# Trainiii_aux.net
KiCad netlist of a schematic drawn in EAGLE
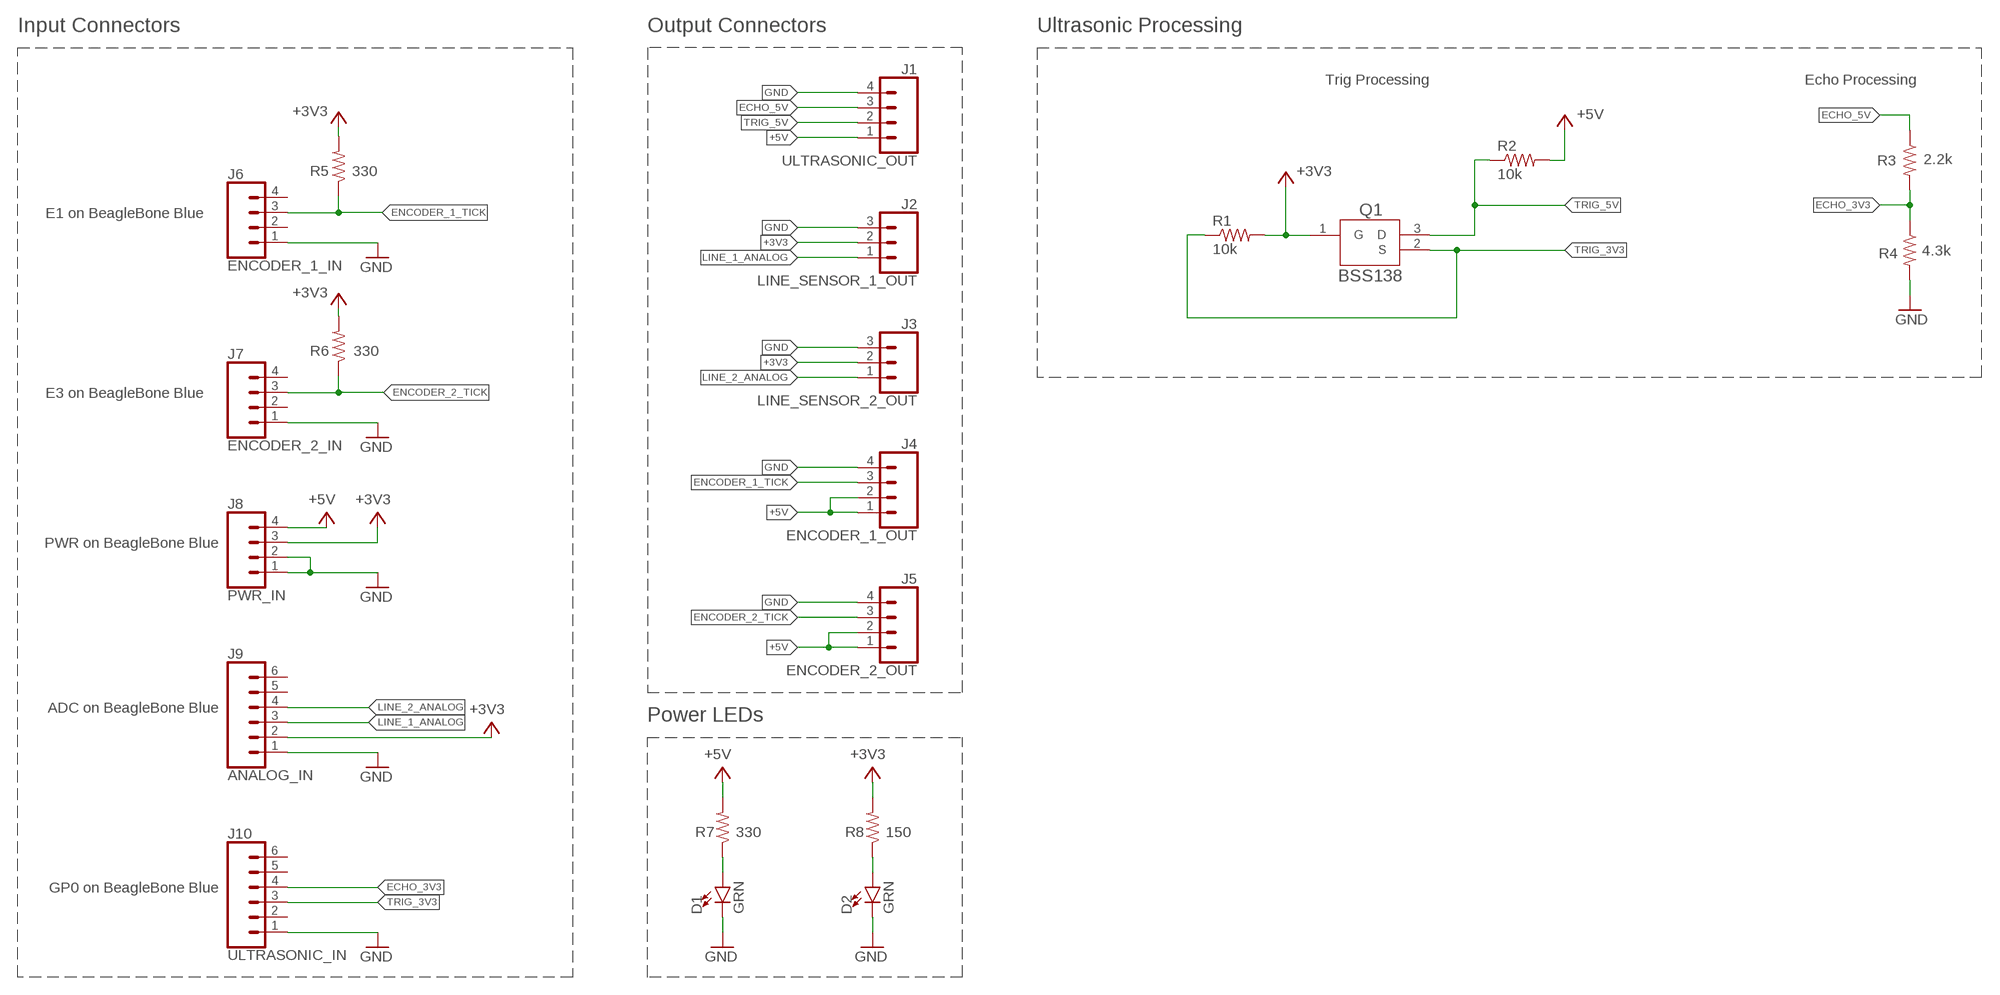
[diagram p0: schematic, sheet 1]

(export (version "E")
  (design (tool "Eeschema 10.0.6"))
  (components
    (comp (ref "D1")
      (value "GRN")
      (footprint "eagle-import:LED-0603")
      (libsource (lib "eagle-import") (part "LED0603"))
    )
    (comp (ref "D2")
      (value "GRN")
      (footprint "eagle-import:LED-0603")
      (libsource (lib "eagle-import") (part "LED0603"))
    )
    (comp (ref "J1")
      (value "ULTRASONIC_OUT")
      (footprint "eagle-import:1X04")
      (libsource (lib "eagle-import") (part "CONN_04"))
    )
    (comp (ref "J2")
      (value "LINE_SENSOR_1_OUT")
      (footprint "eagle-import:1X03")
      (libsource (lib "eagle-import") (part "CONN_03"))
    )
    (comp (ref "J3")
      (value "LINE_SENSOR_2_OUT")
      (footprint "eagle-import:1X03")
      (libsource (lib "eagle-import") (part "CONN_03"))
    )
    (comp (ref "J4")
      (value "ENCODER_1_OUT")
      (footprint "eagle-import:1X04")
      (libsource (lib "eagle-import") (part "CONN_04"))
    )
    (comp (ref "J5")
      (value "ENCODER_2_OUT")
      (footprint "eagle-import:1X04")
      (libsource (lib "eagle-import") (part "CONN_04"))
    )
    (comp (ref "J6")
      (value "ENCODER_1_IN")
      (footprint "eagle-import:1X04")
      (libsource (lib "eagle-import") (part "CONN_04"))
    )
    (comp (ref "J7")
      (value "ENCODER_2_IN")
      (footprint "eagle-import:1X04")
      (libsource (lib "eagle-import") (part "CONN_04"))
    )
    (comp (ref "J8")
      (value "PWR_IN")
      (footprint "eagle-import:1X04")
      (libsource (lib "eagle-import") (part "CONN_04"))
    )
    (comp (ref "J9")
      (value "ANALOG_IN")
      (footprint "eagle-import:1X06")
      (libsource (lib "eagle-import") (part "CONN_06SILK_FEMALE_PTH"))
    )
    (comp (ref "J10")
      (value "ULTRASONIC_IN")
      (footprint "eagle-import:1X06")
      (libsource (lib "eagle-import") (part "CONN_06SILK_FEMALE_PTH"))
    )
    (comp (ref "Q1")
      (value "BSS138")
      (footprint "eagle-import:SOT-23-3L")
      (libsource (lib "eagle-import") (part "BSS138"))
    )
    (comp (ref "R1")
      (value "10k")
      (footprint "eagle-import:R0603")
      (libsource (lib "eagle-import") (part "R-US_R0603"))
    )
    (comp (ref "R2")
      (value "10k")
      (footprint "eagle-import:R0603")
      (libsource (lib "eagle-import") (part "R-US_R0603"))
    )
    (comp (ref "R3")
      (value "2.2k")
      (footprint "eagle-import:R0603")
      (libsource (lib "eagle-import") (part "R-US_R0603"))
    )
    (comp (ref "R4")
      (value "4.3k")
      (footprint "eagle-import:R0603")
      (libsource (lib "eagle-import") (part "R-US_R0603"))
    )
    (comp (ref "R5")
      (value "330")
      (footprint "eagle-import:R0603")
      (libsource (lib "eagle-import") (part "R-US_R0603"))
    )
    (comp (ref "R6")
      (value "330")
      (footprint "eagle-import:R0603")
      (libsource (lib "eagle-import") (part "R-US_R0603"))
    )
    (comp (ref "R7")
      (value "330")
      (footprint "eagle-import:R0603")
      (libsource (lib "eagle-import") (part "R-US_R0603"))
    )
    (comp (ref "R8")
      (value "150")
      (footprint "eagle-import:R0603")
      (libsource (lib "eagle-import") (part "R-US_R0603"))
    )
  )
  (nets
    (net (code "1") (name "+3V3") (class "Default")
      (node (ref "J2") (pin "2") (pinfunction "2_2") (pintype "passive"))
      (node (ref "J3") (pin "2") (pinfunction "2_2") (pintype "passive"))
      (node (ref "J8") (pin "3") (pinfunction "3_3") (pintype "passive"))
      (node (ref "J9") (pin "2") (pinfunction "2_2") (pintype "passive"))
      (node (ref "Q1") (pin "1") (pinfunction "G_1") (pintype "power_in"))
      (node (ref "R1") (pin "2") (pinfunction "2_2") (pintype "passive"))
      (node (ref "R5") (pin "2") (pinfunction "2_2") (pintype "passive"))
      (node (ref "R6") (pin "2") (pinfunction "2_2") (pintype "passive"))
      (node (ref "R8") (pin "2") (pinfunction "2_2") (pintype "passive"))
    )
    (net (code "2") (name "+5V") (class "Default")
      (node (ref "J1") (pin "1") (pinfunction "1_1") (pintype "passive"))
      (node (ref "J4") (pin "1") (pinfunction "1_1") (pintype "passive"))
      (node (ref "J4") (pin "2") (pinfunction "2_2") (pintype "passive"))
      (node (ref "J5") (pin "1") (pinfunction "1_1") (pintype "passive"))
      (node (ref "J5") (pin "2") (pinfunction "2_2") (pintype "passive"))
      (node (ref "J8") (pin "4") (pinfunction "4_4") (pintype "passive"))
      (node (ref "R2") (pin "2") (pinfunction "2_2") (pintype "passive"))
      (node (ref "R7") (pin "2") (pinfunction "2_2") (pintype "passive"))
    )
    (net (code "3") (name "ECHO_3V3") (class "Default")
      (node (ref "J10") (pin "4") (pinfunction "4_4") (pintype "passive"))
      (node (ref "R3") (pin "2") (pinfunction "2_2") (pintype "passive"))
      (node (ref "R4") (pin "1") (pinfunction "1_1") (pintype "passive"))
    )
    (net (code "4") (name "ECHO_5V") (class "Default")
      (node (ref "J1") (pin "3") (pinfunction "3_3") (pintype "passive"))
      (node (ref "R3") (pin "1") (pinfunction "1_1") (pintype "passive"))
    )
    (net (code "5") (name "ENCODER_1_TICK") (class "Default")
      (node (ref "J4") (pin "3") (pinfunction "3_3") (pintype "passive"))
      (node (ref "J6") (pin "3") (pinfunction "3_3") (pintype "passive"))
      (node (ref "R5") (pin "1") (pinfunction "1_1") (pintype "passive"))
    )
    (net (code "6") (name "ENCODER_2_TICK") (class "Default")
      (node (ref "J5") (pin "3") (pinfunction "3_3") (pintype "passive"))
      (node (ref "J7") (pin "3") (pinfunction "3_3") (pintype "passive"))
      (node (ref "R6") (pin "1") (pinfunction "1_1") (pintype "passive"))
    )
    (net (code "7") (name "GND") (class "Default")
      (node (ref "D1") (pin "C") (pinfunction "C_C") (pintype "passive"))
      (node (ref "D2") (pin "C") (pinfunction "C_C") (pintype "passive"))
      (node (ref "J1") (pin "4") (pinfunction "4_4") (pintype "passive"))
      (node (ref "J10") (pin "1") (pinfunction "1_1") (pintype "passive"))
      (node (ref "J2") (pin "3") (pinfunction "3_3") (pintype "passive"))
      (node (ref "J3") (pin "3") (pinfunction "3_3") (pintype "passive"))
      (node (ref "J4") (pin "4") (pinfunction "4_4") (pintype "passive"))
      (node (ref "J5") (pin "4") (pinfunction "4_4") (pintype "passive"))
      (node (ref "J6") (pin "1") (pinfunction "1_1") (pintype "passive"))
      (node (ref "J7") (pin "1") (pinfunction "1_1") (pintype "passive"))
      (node (ref "J8") (pin "1") (pinfunction "1_1") (pintype "passive"))
      (node (ref "J8") (pin "2") (pinfunction "2_2") (pintype "passive"))
      (node (ref "J9") (pin "1") (pinfunction "1_1") (pintype "passive"))
      (node (ref "R4") (pin "2") (pinfunction "2_2") (pintype "passive"))
    )
    (net (code "8") (name "LINE_1_ANALOG") (class "Default")
      (node (ref "J2") (pin "1") (pinfunction "1_1") (pintype "passive"))
      (node (ref "J9") (pin "3") (pinfunction "3_3") (pintype "passive"))
    )
    (net (code "9") (name "LINE_2_ANALOG") (class "Default")
      (node (ref "J3") (pin "1") (pinfunction "1_1") (pintype "passive"))
      (node (ref "J9") (pin "4") (pinfunction "4_4") (pintype "passive"))
    )
    (net (code "10") (name "Net-(D1-PadA)") (class "Default")
      (node (ref "D1") (pin "A") (pinfunction "A_A") (pintype "passive"))
      (node (ref "R7") (pin "1") (pinfunction "1_1") (pintype "passive"))
    )
    (net (code "11") (name "Net-(D2-PadA)") (class "Default")
      (node (ref "D2") (pin "A") (pinfunction "A_A") (pintype "passive"))
      (node (ref "R8") (pin "1") (pinfunction "1_1") (pintype "passive"))
    )
    (net (code "12") (name "TRIG_3V3") (class "Default")
      (node (ref "J10") (pin "3") (pinfunction "3_3") (pintype "passive"))
      (node (ref "Q1") (pin "2") (pinfunction "S_2") (pintype "input"))
      (node (ref "R1") (pin "1") (pinfunction "1_1") (pintype "passive"))
    )
    (net (code "13") (name "TRIG_5V") (class "Default")
      (node (ref "J1") (pin "2") (pinfunction "2_2") (pintype "passive"))
      (node (ref "Q1") (pin "3") (pinfunction "D_3") (pintype "output"))
      (node (ref "R2") (pin "1") (pinfunction "1_1") (pintype "passive"))
    )
    (net (code "14") (name "unconnected-(J6-Pad2)") (class "Default")
      (node (ref "J6") (pin "2") (pinfunction "2_2") (pintype "passive"))
    )
    (net (code "15") (name "unconnected-(J6-Pad4)") (class "Default")
      (node (ref "J6") (pin "4") (pinfunction "4_4") (pintype "passive"))
    )
    (net (code "16") (name "unconnected-(J7-Pad2)") (class "Default")
      (node (ref "J7") (pin "2") (pinfunction "2_2") (pintype "passive"))
    )
    (net (code "17") (name "unconnected-(J7-Pad4)") (class "Default")
      (node (ref "J7") (pin "4") (pinfunction "4_4") (pintype "passive"))
    )
    (net (code "18") (name "unconnected-(J9-Pad5)") (class "Default")
      (node (ref "J9") (pin "5") (pinfunction "5_5") (pintype "passive"))
    )
    (net (code "19") (name "unconnected-(J9-Pad6)") (class "Default")
      (node (ref "J9") (pin "6") (pinfunction "6_6") (pintype "passive"))
    )
    (net (code "20") (name "unconnected-(J10-Pad2)") (class "Default")
      (node (ref "J10") (pin "2") (pinfunction "2_2") (pintype "passive"))
    )
    (net (code "21") (name "unconnected-(J10-Pad5)") (class "Default")
      (node (ref "J10") (pin "5") (pinfunction "5_5") (pintype "passive"))
    )
    (net (code "22") (name "unconnected-(J10-Pad6)") (class "Default")
      (node (ref "J10") (pin "6") (pinfunction "6_6") (pintype "passive"))
    )
  )
)
